# 04_LCD.net
KiCad netlist of a schematic drawn in Altium Designer
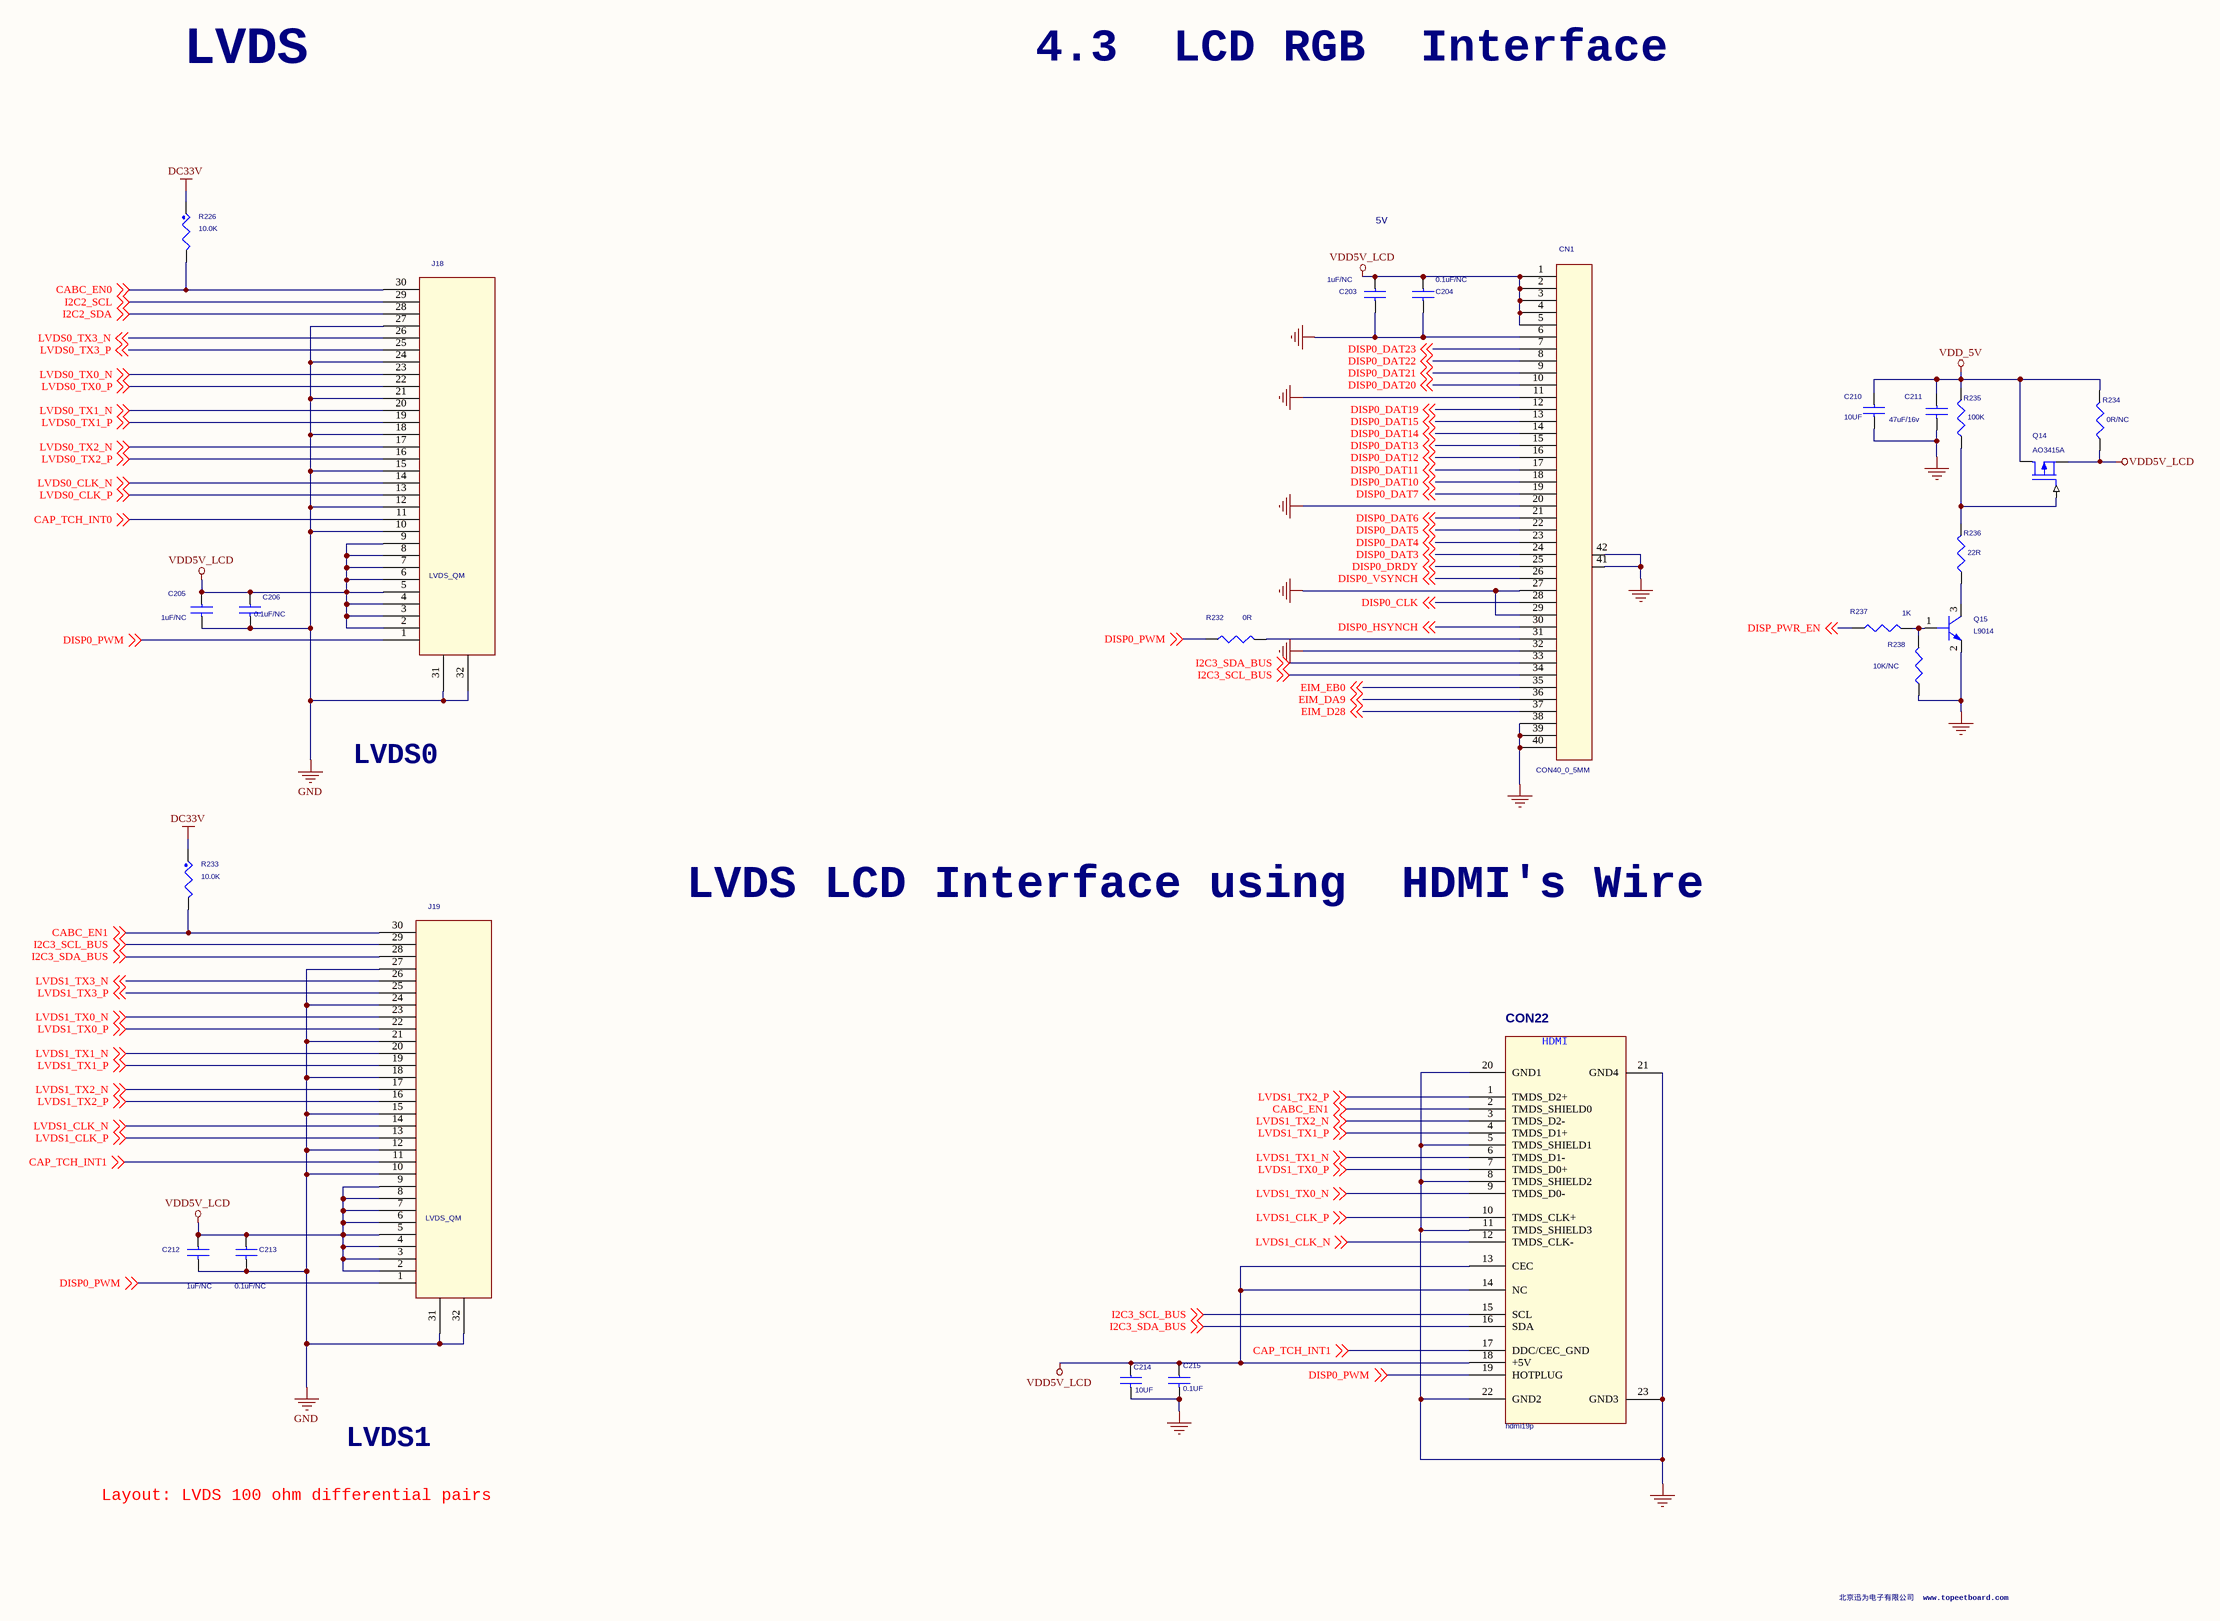
[diagram p0: 04 LCD.SchDoc]

(export (version "E")
  (design (tool "Eeschema 10.0.6"))
  (components
    (comp (ref "C203") (value "1uF/NC") (footprint "C0603") (libsource (lib "*") (part "C0603_0_Dup1")))
    (comp (ref "C204") (value "0.1uF/NC") (footprint "C0603") (libsource (lib "*") (part "C0603_0_Dup1")))
    (comp (ref "C205") (value "1uF/NC") (footprint "C0603") (libsource (lib "*") (part "C0603_0_Dup1")))
    (comp (ref "C206") (value "0.1uF/NC") (footprint "C0603") (libsource (lib "*") (part "C0603_0_Dup1")))
    (comp (ref "C210") (value "10UF") (footprint "C1608") (libsource (lib "*") (part "C1608_Dup1")))
    (comp (ref "C211") (value "47uF/16v") (footprint "C1608") (libsource (lib "*") (part "C1608_Dup1")))
    (comp (ref "C212") (value "1uF/NC") (footprint "C0603") (libsource (lib "*") (part "C0603_0_Dup1")))
    (comp (ref "C213") (value "0.1uF/NC") (footprint "C0603") (libsource (lib "*") (part "C0603_0_Dup1")))
    (comp (ref "C214") (value "10UF") (footprint "C1608") (libsource (lib "*") (part "C1608_Dup1")))
    (comp (ref "C215") (value "0.1UF") (footprint "C0402") (libsource (lib "*") (part "C0402_0")))
    (comp (ref "CN1")
      (value "CON40_0_5MM")
      (footprint "CON60_0_5MM")
      (libsource (lib "*") (part "CON40_0_1"))
    )
    (comp (ref "CON22") (value "hdmi19p") (footprint "MD60-19P") (libsource (lib "*") (part "MD60-19P_6")))
    (comp (ref "J18") (value "LVDS_QM") (libsource (lib "*") (part "LVDS_QM_2")))
    (comp (ref "J19") (value "LVDS_QM") (libsource (lib "*") (part "LVDS_QM_2")))
    (comp (ref "Q14") (value "AO3415A") (libsource (lib "*") (part "MOSFET P")))
    (comp (ref "Q15") (value "L9014") (libsource (lib "*") (part "L14P2/TO_1")))
    (comp (ref "R226")
      (value "10.0K")
      (description "RES MF 10.0K 1/16W 1% AEC-Q200 0402")
      (fields (field (name "TOLERANCE") "1%"))
      (libsource (lib "*") (part "RES_Dup1"))
    )
    (comp (ref "R232") (value "0R") (footprint "R1005") (libsource (lib "*") (part "R1005_0_Dup2")))
    (comp (ref "R233")
      (value "10.0K")
      (description "RES MF 10.0K 1/16W 1% AEC-Q200 0402")
      (fields (field (name "TOLERANCE") "1%"))
      (libsource (lib "*") (part "RES_Dup1"))
    )
    (comp (ref "R234") (value "0R/NC") (footprint "R1005") (libsource (lib "*") (part "R1005_0_Dup2")))
    (comp (ref "R235") (value "100K") (footprint "R1005") (libsource (lib "*") (part "R1005_0_Dup2")))
    (comp (ref "R236") (value "22R") (footprint "R1005") (libsource (lib "*") (part "R1005_0_Dup2")))
    (comp (ref "R237") (value "1K") (footprint "R1005") (libsource (lib "*") (part "R1005_0_Dup2")))
    (comp (ref "R238") (value "10K/NC") (footprint "R1005") (libsource (lib "*") (part "R1005_0_Dup2")))
  )
  (nets
    (net (code "1") (name "CABC_EN0") (class "Default")
      (node (ref "J18") (pin "30") (pinfunction "$PIN0_30") (pintype "passive"))
      (node (ref "R226") (pin "2") (pinfunction "2_2") (pintype "passive"))
    )
    (net (code "2") (name "CABC_EN1") (class "Default")
      (node (ref "CON22") (pin "2") (pinfunction "TMDS_SHIELD0_2") (pintype "passive"))
      (node (ref "J19") (pin "30") (pinfunction "$PIN0_30") (pintype "passive"))
      (node (ref "R233") (pin "2") (pinfunction "2_2") (pintype "passive"))
    )
    (net (code "3") (name "CAP_TCH_INT0") (class "Default")
      (node (ref "J18") (pin "11") (pinfunction "$PIN19_11") (pintype "passive"))
    )
    (net (code "4") (name "CAP_TCH_INT1") (class "Default")
      (node (ref "CON22") (pin "17") (pinfunction "DDC/CEC_GND_17") (pintype "passive"))
      (node (ref "J19") (pin "11") (pinfunction "$PIN19_11") (pintype "passive"))
    )
    (net (code "5") (name "DC33V") (class "Default")
      (node (ref "R226") (pin "1") (pinfunction "1_1") (pintype "passive"))
      (node (ref "R233") (pin "1") (pinfunction "1_1") (pintype "passive"))
    )
    (net (code "6") (name "DISP0_CLK") (class "Default")
      (node (ref "CN1") (pin "28") (pinfunction "28_28") (pintype "passive"))
    )
    (net (code "7") (name "DISP0_DAT3") (class "Default")
      (node (ref "CN1") (pin "24") (pinfunction "24_24") (pintype "passive"))
    )
    (net (code "8") (name "DISP0_DAT4") (class "Default")
      (node (ref "CN1") (pin "23") (pinfunction "23_23") (pintype "passive"))
    )
    (net (code "9") (name "DISP0_DAT5") (class "Default")
      (node (ref "CN1") (pin "22") (pinfunction "22_22") (pintype "passive"))
    )
    (net (code "10") (name "DISP0_DAT6") (class "Default")
      (node (ref "CN1") (pin "21") (pinfunction "21_21") (pintype "passive"))
    )
    (net (code "11") (name "DISP0_DAT7") (class "Default")
      (node (ref "CN1") (pin "19") (pinfunction "19_19") (pintype "passive"))
    )
    (net (code "12") (name "DISP0_DAT10") (class "Default")
      (node (ref "CN1") (pin "18") (pinfunction "18_18") (pintype "passive"))
    )
    (net (code "13") (name "DISP0_DAT11") (class "Default")
      (node (ref "CN1") (pin "17") (pinfunction "17_17") (pintype "passive"))
    )
    (net (code "14") (name "DISP0_DAT12") (class "Default")
      (node (ref "CN1") (pin "16") (pinfunction "16_16") (pintype "passive"))
    )
    (net (code "15") (name "DISP0_DAT13") (class "Default")
      (node (ref "CN1") (pin "15") (pinfunction "15_15") (pintype "passive"))
    )
    (net (code "16") (name "DISP0_DAT14") (class "Default")
      (node (ref "CN1") (pin "14") (pinfunction "14_14") (pintype "passive"))
    )
    (net (code "17") (name "DISP0_DAT15") (class "Default")
      (node (ref "CN1") (pin "13") (pinfunction "13_13") (pintype "passive"))
    )
    (net (code "18") (name "DISP0_DAT19") (class "Default")
      (node (ref "CN1") (pin "12") (pinfunction "12_12") (pintype "passive"))
    )
    (net (code "19") (name "DISP0_DAT20") (class "Default")
      (node (ref "CN1") (pin "10") (pinfunction "10_10") (pintype "passive"))
    )
    (net (code "20") (name "DISP0_DAT21") (class "Default")
      (node (ref "CN1") (pin "9") (pinfunction "9_9") (pintype "passive"))
    )
    (net (code "21") (name "DISP0_DAT22") (class "Default")
      (node (ref "CN1") (pin "8") (pinfunction "8_8") (pintype "passive"))
    )
    (net (code "22") (name "DISP0_DAT23") (class "Default")
      (node (ref "CN1") (pin "7") (pinfunction "7_7") (pintype "passive"))
    )
    (net (code "23") (name "DISP0_DRDY") (class "Default")
      (node (ref "CN1") (pin "25") (pinfunction "25_25") (pintype "passive"))
    )
    (net (code "24") (name "DISP0_HSYNCH") (class "Default")
      (node (ref "CN1") (pin "30") (pinfunction "30_30") (pintype "passive"))
    )
    (net (code "25") (name "DISP0_PWM") (class "Default")
      (node (ref "CON22") (pin "19") (pinfunction "HOTPLUG_19") (pintype "passive"))
      (node (ref "J18") (pin "1") (pinfunction "$PIN30_1") (pintype "passive"))
      (node (ref "J19") (pin "1") (pinfunction "$PIN30_1") (pintype "passive"))
      (node (ref "R232") (pin "1") (pinfunction "1_1") (pintype "passive"))
    )
    (net (code "26") (name "DISP0_VSYNCH") (class "Default")
      (node (ref "CN1") (pin "26") (pinfunction "26_26") (pintype "passive"))
    )
    (net (code "27") (name "DISP_PWR_EN") (class "Default")
      (node (ref "R237") (pin "2") (pinfunction "2_2") (pintype "passive"))
    )
    (net (code "28") (name "EIM_D28") (class "Default")
      (node (ref "CN1") (pin "37") (pinfunction "37_37") (pintype "passive"))
    )
    (net (code "29") (name "EIM_DA9") (class "Default")
      (node (ref "CN1") (pin "36") (pinfunction "36_36") (pintype "passive"))
    )
    (net (code "30") (name "EIM_EB0") (class "Default")
      (node (ref "CN1") (pin "35") (pinfunction "35_35") (pintype "passive"))
    )
    (net (code "31") (name "GND") (class "Default")
      (node (ref "C203") (pin "2") (pinfunction "2_2") (pintype "passive"))
      (node (ref "C204") (pin "2") (pinfunction "2_2") (pintype "passive"))
      (node (ref "C205") (pin "2") (pinfunction "2_2") (pintype "passive"))
      (node (ref "C206") (pin "2") (pinfunction "2_2") (pintype "passive"))
      (node (ref "C210") (pin "2") (pinfunction "2_2") (pintype "passive"))
      (node (ref "C211") (pin "2") (pinfunction "2_2") (pintype "passive"))
      (node (ref "C212") (pin "2") (pinfunction "2_2") (pintype "passive"))
      (node (ref "C213") (pin "2") (pinfunction "2_2") (pintype "passive"))
      (node (ref "C214") (pin "2") (pinfunction "2_2") (pintype "passive"))
      (node (ref "C215") (pin "2") (pinfunction "2_2") (pintype "passive"))
      (node (ref "CN1") (pin "11") (pinfunction "11_11") (pintype "passive"))
      (node (ref "CN1") (pin "20") (pinfunction "20_20") (pintype "passive"))
      (node (ref "CN1") (pin "27") (pinfunction "27_27") (pintype "passive"))
      (node (ref "CN1") (pin "29") (pinfunction "29_29") (pintype "passive"))
      (node (ref "CN1") (pin "32") (pinfunction "32_32") (pintype "passive"))
      (node (ref "CN1") (pin "38") (pinfunction "38_38") (pintype "passive"))
      (node (ref "CN1") (pin "39") (pinfunction "39_39") (pintype "passive"))
      (node (ref "CN1") (pin "40") (pinfunction "40_40") (pintype "passive"))
      (node (ref "CN1") (pin "41") (pinfunction "41_41") (pintype "passive"))
      (node (ref "CN1") (pin "42") (pinfunction "42_42") (pintype "passive"))
      (node (ref "CN1") (pin "6") (pinfunction "6_6") (pintype "passive"))
      (node (ref "CON22") (pin "11") (pinfunction "TMDS_SHIELD3_11") (pintype "passive"))
      (node (ref "CON22") (pin "20") (pinfunction "GND1_20") (pintype "power_in"))
      (node (ref "CON22") (pin "21") (pinfunction "GND4_21") (pintype "power_in"))
      (node (ref "CON22") (pin "22") (pinfunction "GND2_22") (pintype "power_in"))
      (node (ref "CON22") (pin "23") (pinfunction "GND3_23") (pintype "power_in"))
      (node (ref "CON22") (pin "5") (pinfunction "TMDS_SHIELD1_5") (pintype "passive"))
      (node (ref "CON22") (pin "8") (pinfunction "TMDS_SHIELD2_8") (pintype "passive"))
      (node (ref "J18") (pin "10") (pinfunction "$PIN20_10") (pintype "passive"))
      (node (ref "J18") (pin "12") (pinfunction "$PIN18_12") (pintype "passive"))
      (node (ref "J18") (pin "15") (pinfunction "$PIN15_15") (pintype "passive"))
      (node (ref "J18") (pin "18") (pinfunction "$PIN12_18") (pintype "passive"))
      (node (ref "J18") (pin "21") (pinfunction "$PIN9_21") (pintype "passive"))
      (node (ref "J18") (pin "24") (pinfunction "$PIN6_24") (pintype "passive"))
      (node (ref "J18") (pin "27") (pinfunction "$PIN3_27") (pintype "passive"))
      (node (ref "J18") (pin "31") (pinfunction "31_31") (pintype "passive"))
      (node (ref "J18") (pin "32") (pinfunction "32_32") (pintype "passive"))
      (node (ref "J19") (pin "10") (pinfunction "$PIN20_10") (pintype "passive"))
      (node (ref "J19") (pin "12") (pinfunction "$PIN18_12") (pintype "passive"))
      (node (ref "J19") (pin "15") (pinfunction "$PIN15_15") (pintype "passive"))
      (node (ref "J19") (pin "18") (pinfunction "$PIN12_18") (pintype "passive"))
      (node (ref "J19") (pin "21") (pinfunction "$PIN9_21") (pintype "passive"))
      (node (ref "J19") (pin "24") (pinfunction "$PIN6_24") (pintype "passive"))
      (node (ref "J19") (pin "27") (pinfunction "$PIN3_27") (pintype "passive"))
      (node (ref "J19") (pin "31") (pinfunction "31_31") (pintype "passive"))
      (node (ref "J19") (pin "32") (pinfunction "32_32") (pintype "passive"))
      (node (ref "Q15") (pin "2") (pinfunction "EMITTER_2") (pintype "passive"))
      (node (ref "R238") (pin "2") (pinfunction "2_2") (pintype "passive"))
    )
    (net (code "32") (name "I2C2_SCL") (class "Default")
      (node (ref "J18") (pin "29") (pinfunction "$PIN1_29") (pintype "passive"))
    )
    (net (code "33") (name "I2C2_SDA") (class "Default")
      (node (ref "J18") (pin "28") (pinfunction "$PIN2_28") (pintype "passive"))
    )
    (net (code "34") (name "I2C3_SCL_BUS") (class "Default")
      (node (ref "CN1") (pin "34") (pinfunction "34_34") (pintype "passive"))
      (node (ref "CON22") (pin "15") (pinfunction "SCL_15") (pintype "passive"))
      (node (ref "J19") (pin "29") (pinfunction "$PIN1_29") (pintype "passive"))
    )
    (net (code "35") (name "I2C3_SDA_BUS") (class "Default")
      (node (ref "CN1") (pin "33") (pinfunction "33_33") (pintype "passive"))
      (node (ref "CON22") (pin "16") (pinfunction "SDA_16") (pintype "passive"))
      (node (ref "J19") (pin "28") (pinfunction "$PIN2_28") (pintype "passive"))
    )
    (net (code "36") (name "LVDS0_CLK_N") (class "Default")
      (node (ref "J18") (pin "14") (pinfunction "$PIN16_14") (pintype "passive"))
    )
    (net (code "37") (name "LVDS0_CLK_P") (class "Default")
      (node (ref "J18") (pin "13") (pinfunction "$PIN17_13") (pintype "passive"))
    )
    (net (code "38") (name "LVDS0_TX0_N") (class "Default")
      (node (ref "J18") (pin "23") (pinfunction "$PIN7_23") (pintype "passive"))
    )
    (net (code "39") (name "LVDS0_TX0_P") (class "Default")
      (node (ref "J18") (pin "22") (pinfunction "$PIN8_22") (pintype "passive"))
    )
    (net (code "40") (name "LVDS0_TX1_N") (class "Default")
      (node (ref "J18") (pin "20") (pinfunction "$PIN10_20") (pintype "passive"))
    )
    (net (code "41") (name "LVDS0_TX1_P") (class "Default")
      (node (ref "J18") (pin "19") (pinfunction "$PIN11_19") (pintype "passive"))
    )
    (net (code "42") (name "LVDS0_TX2_N") (class "Default")
      (node (ref "J18") (pin "17") (pinfunction "$PIN13_17") (pintype "passive"))
    )
    (net (code "43") (name "LVDS0_TX2_P") (class "Default")
      (node (ref "J18") (pin "16") (pinfunction "$PIN14_16") (pintype "passive"))
    )
    (net (code "44") (name "LVDS0_TX3_N") (class "Default")
      (node (ref "J18") (pin "26") (pinfunction "$PIN4_26") (pintype "passive"))
    )
    (net (code "45") (name "LVDS0_TX3_P") (class "Default")
      (node (ref "J18") (pin "25") (pinfunction "$PIN5_25") (pintype "passive"))
    )
    (net (code "46") (name "LVDS1_CLK_N") (class "Default")
      (node (ref "CON22") (pin "12") (pinfunction "TMDS_CLK-_12") (pintype "passive"))
      (node (ref "J19") (pin "14") (pinfunction "$PIN16_14") (pintype "passive"))
    )
    (net (code "47") (name "LVDS1_CLK_P") (class "Default")
      (node (ref "CON22") (pin "10") (pinfunction "TMDS_CLK+_10") (pintype "passive"))
      (node (ref "J19") (pin "13") (pinfunction "$PIN17_13") (pintype "passive"))
    )
    (net (code "48") (name "LVDS1_TX0_N") (class "Default")
      (node (ref "CON22") (pin "9") (pinfunction "TMDS_D0-_9") (pintype "power_in"))
      (node (ref "J19") (pin "23") (pinfunction "$PIN7_23") (pintype "passive"))
    )
    (net (code "49") (name "LVDS1_TX0_P") (class "Default")
      (node (ref "CON22") (pin "7") (pinfunction "TMDS_D0+_7") (pintype "passive"))
      (node (ref "J19") (pin "22") (pinfunction "$PIN8_22") (pintype "passive"))
    )
    (net (code "50") (name "LVDS1_TX1_N") (class "Default")
      (node (ref "CON22") (pin "6") (pinfunction "TMDS_D1-_6") (pintype "passive"))
      (node (ref "J19") (pin "20") (pinfunction "$PIN10_20") (pintype "passive"))
    )
    (net (code "51") (name "LVDS1_TX1_P") (class "Default")
      (node (ref "CON22") (pin "4") (pinfunction "TMDS_D1+_4") (pintype "passive"))
      (node (ref "J19") (pin "19") (pinfunction "$PIN11_19") (pintype "passive"))
    )
    (net (code "52") (name "LVDS1_TX2_N") (class "Default")
      (node (ref "CON22") (pin "3") (pinfunction "TMDS_D2-_3") (pintype "passive"))
      (node (ref "J19") (pin "17") (pinfunction "$PIN13_17") (pintype "passive"))
    )
    (net (code "53") (name "LVDS1_TX2_P") (class "Default")
      (node (ref "CON22") (pin "1") (pinfunction "TMDS_D2+_1") (pintype "passive"))
      (node (ref "J19") (pin "16") (pinfunction "$PIN14_16") (pintype "passive"))
    )
    (net (code "54") (name "LVDS1_TX3_N") (class "Default")
      (node (ref "J19") (pin "26") (pinfunction "$PIN4_26") (pintype "passive"))
    )
    (net (code "55") (name "LVDS1_TX3_P") (class "Default")
      (node (ref "J19") (pin "25") (pinfunction "$PIN5_25") (pintype "passive"))
    )
    (net (code "56") (name "Net-(CN1-Pad31)") (class "Default")
      (node (ref "CN1") (pin "31") (pinfunction "31_31") (pintype "passive"))
      (node (ref "R232") (pin "2") (pinfunction "2_2") (pintype "passive"))
    )
    (net (code "57") (name "Net-(Q14-GATE)") (class "Default")
      (node (ref "Q14") (pin "1") (pinfunction "GATE_1") (pintype "input"))
      (node (ref "R235") (pin "2") (pinfunction "2_2") (pintype "passive"))
      (node (ref "R236") (pin "1") (pinfunction "1_1") (pintype "passive"))
    )
    (net (code "58") (name "Net-(Q15-BASE)") (class "Default")
      (node (ref "Q15") (pin "1") (pinfunction "BASE_1") (pintype "passive"))
      (node (ref "R237") (pin "1") (pinfunction "1_1") (pintype "passive"))
      (node (ref "R238") (pin "1") (pinfunction "1_1") (pintype "passive"))
    )
    (net (code "59") (name "Net-(Q15-COLLECTOR)") (class "Default")
      (node (ref "Q15") (pin "3") (pinfunction "COLLECTOR_3") (pintype "passive"))
      (node (ref "R236") (pin "2") (pinfunction "2_2") (pintype "passive"))
    )
    (net (code "60") (name "VDD5V_LCD") (class "Default")
      (node (ref "C203") (pin "1") (pinfunction "1_1") (pintype "passive"))
      (node (ref "C204") (pin "1") (pinfunction "1_1") (pintype "passive"))
      (node (ref "C205") (pin "1") (pinfunction "1_1") (pintype "passive"))
      (node (ref "C206") (pin "1") (pinfunction "1_1") (pintype "passive"))
      (node (ref "C212") (pin "1") (pinfunction "1_1") (pintype "passive"))
      (node (ref "C213") (pin "1") (pinfunction "1_1") (pintype "passive"))
      (node (ref "C214") (pin "1") (pinfunction "1_1") (pintype "passive"))
      (node (ref "C215") (pin "1") (pinfunction "1_1") (pintype "passive"))
      (node (ref "CN1") (pin "1") (pinfunction "1_1") (pintype "passive"))
      (node (ref "CN1") (pin "2") (pinfunction "2_2") (pintype "passive"))
      (node (ref "CN1") (pin "3") (pinfunction "3_3") (pintype "passive"))
      (node (ref "CN1") (pin "4") (pinfunction "4_4") (pintype "passive"))
      (node (ref "CN1") (pin "5") (pinfunction "5_5") (pintype "passive"))
      (node (ref "CON22") (pin "13") (pinfunction "CEC_13") (pintype "passive"))
      (node (ref "CON22") (pin "14") (pinfunction "NC_14") (pintype "passive"))
      (node (ref "CON22") (pin "18") (pinfunction "+5V_18") (pintype "passive"))
      (node (ref "J18") (pin "2") (pinfunction "$PIN29_2") (pintype "passive"))
      (node (ref "J18") (pin "3") (pinfunction "$PIN28_3") (pintype "passive"))
      (node (ref "J18") (pin "4") (pinfunction "$PIN27_4") (pintype "passive"))
      (node (ref "J18") (pin "5") (pinfunction "$PIN26_5") (pintype "passive"))
      (node (ref "J18") (pin "6") (pinfunction "$PIN25_6") (pintype "passive"))
      (node (ref "J18") (pin "7") (pinfunction "$PIN24_7") (pintype "passive"))
      (node (ref "J18") (pin "8") (pinfunction "$PIN22_8") (pintype "passive"))
      (node (ref "J18") (pin "9") (pinfunction "$PIN21_9") (pintype "passive"))
      (node (ref "J19") (pin "2") (pinfunction "$PIN29_2") (pintype "passive"))
      (node (ref "J19") (pin "3") (pinfunction "$PIN28_3") (pintype "passive"))
      (node (ref "J19") (pin "4") (pinfunction "$PIN27_4") (pintype "passive"))
      (node (ref "J19") (pin "5") (pinfunction "$PIN26_5") (pintype "passive"))
      (node (ref "J19") (pin "6") (pinfunction "$PIN25_6") (pintype "passive"))
      (node (ref "J19") (pin "7") (pinfunction "$PIN24_7") (pintype "passive"))
      (node (ref "J19") (pin "8") (pinfunction "$PIN22_8") (pintype "passive"))
      (node (ref "J19") (pin "9") (pinfunction "$PIN21_9") (pintype "passive"))
      (node (ref "Q14") (pin "3") (pinfunction "SOURCE_3") (pintype "passive"))
      (node (ref "R234") (pin "2") (pinfunction "2_2") (pintype "passive"))
    )
    (net (code "61") (name "VDD_5V") (class "Default")
      (node (ref "C210") (pin "1") (pinfunction "1_1") (pintype "passive"))
      (node (ref "C211") (pin "1") (pinfunction "1_1") (pintype "passive"))
      (node (ref "Q14") (pin "2") (pinfunction "DRAIN_2") (pintype "passive"))
      (node (ref "R234") (pin "1") (pinfunction "1_1") (pintype "passive"))
      (node (ref "R235") (pin "1") (pinfunction "1_1") (pintype "passive"))
    )
  )
)
